# M_B_adapter_414.net
KiCad netlist of a schematic drawn in EAGLE
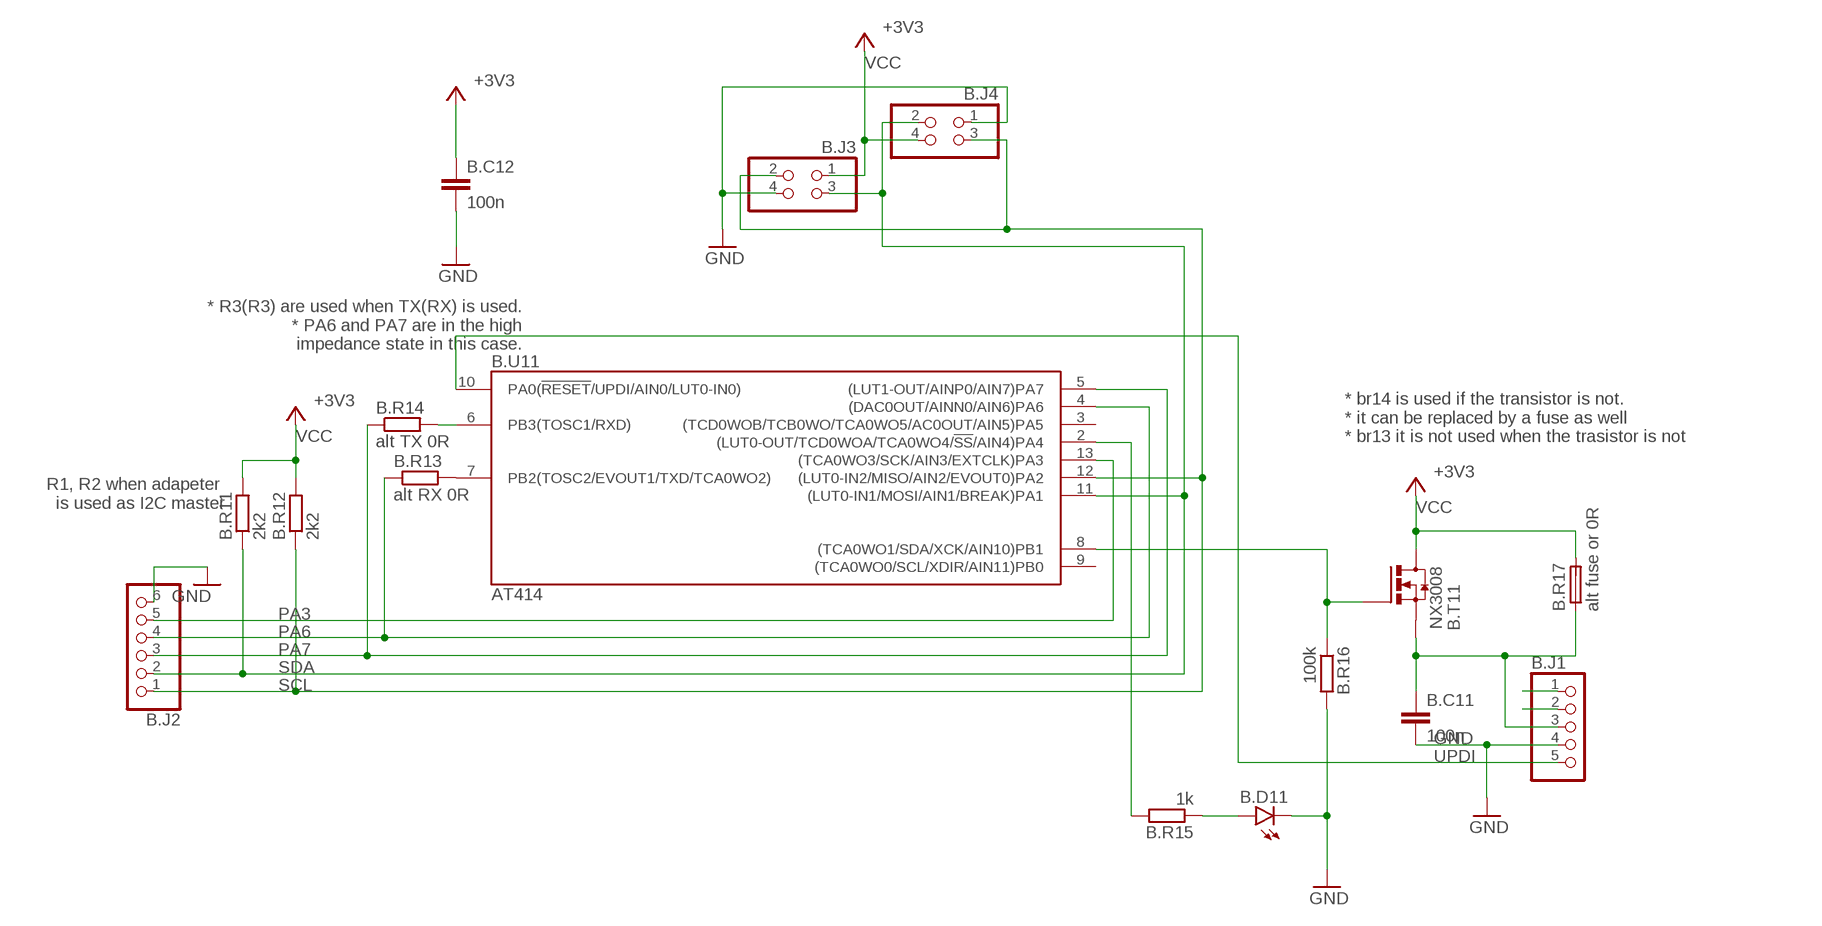
[diagram p0: schematic, sheet 1]

(export (version "E")
  (design (tool "Eeschema 10.0.6"))
  (components
    (comp (ref "B.C11")
      (value "100n")
      (footprint "eagle-import:C0603")
      (libsource (lib "eagle-import") (part "C-EUC0603"))
    )
    (comp (ref "B.C12")
      (value "100n")
      (footprint "eagle-import:C0603")
      (libsource (lib "eagle-import") (part "C-EUC0603"))
    )
    (comp (ref "B.D11")
      (value "LEDCHIP-LED0603")
      (footprint "eagle-import:CHIP-LED0603")
      (libsource (lib "eagle-import") (part "LEDCHIP-LED0603"))
    )
    (comp (ref "B.J1")
      (value "PINHD-1X5")
      (footprint "eagle-import:1X05")
      (libsource (lib "eagle-import") (part "PINHD-1X5"))
    )
    (comp (ref "B.J2")
      (value "PINHD-1X6")
      (footprint "eagle-import:1X06")
      (libsource (lib "eagle-import") (part "PINHD-1X6"))
    )
    (comp (ref "B.J3")
      (value "PINHD-2X2")
      (footprint "eagle-import:2X02")
      (libsource (lib "eagle-import") (part "PINHD-2X2"))
    )
    (comp (ref "B.J4")
      (value "PINHD-2X2")
      (footprint "eagle-import:2X02")
      (libsource (lib "eagle-import") (part "PINHD-2X2"))
    )
    (comp (ref "B.R11")
      (value "2k2")
      (footprint "eagle-import:R0603")
      (libsource (lib "eagle-import") (part "R-EU_R0603"))
    )
    (comp (ref "B.R12")
      (value "2k2")
      (footprint "eagle-import:R0603")
      (libsource (lib "eagle-import") (part "R-EU_R0603"))
    )
    (comp (ref "B.R13")
      (value "alt RX 0R")
      (footprint "eagle-import:R0603")
      (libsource (lib "eagle-import") (part "R-EU_R0603"))
    )
    (comp (ref "B.R14")
      (value "alt TX 0R")
      (footprint "eagle-import:R0603")
      (libsource (lib "eagle-import") (part "R-EU_R0603"))
    )
    (comp (ref "B.R15")
      (value "1k")
      (footprint "eagle-import:R0603")
      (libsource (lib "eagle-import") (part "R-EU_R0603"))
    )
    (comp (ref "B.R16")
      (value "100k")
      (footprint "eagle-import:R0603")
      (libsource (lib "eagle-import") (part "R-EU_R0603"))
    )
    (comp (ref "B.R17")
      (value "alt fuse or 0R")
      (footprint "eagle-import:FUSE")
      (libsource (lib "eagle-import") (part "FUSE"))
    )
    (comp (ref "B.T11")
      (value "NX3008")
      (footprint "eagle-import:SO23")
      (libsource (lib "eagle-import") (part "N-MOSFET"))
    )
    (comp (ref "B.U11")
      (value "AT414")
      (footprint "eagle-import:SO14")
      (libsource (lib "eagle-import") (part "ATTINY14-SSN4"))
    )
  )
  (nets
    (net (code "1") (name "+3V3") (class "Default")
      (node (ref "B.C12") (pin "1") (pinfunction "1_1") (pintype "passive"))
      (node (ref "B.J3") (pin "1") (pinfunction "1_1") (pintype "passive"))
      (node (ref "B.J4") (pin "4") (pinfunction "4_4") (pintype "passive"))
      (node (ref "B.R11") (pin "2") (pinfunction "2_2") (pintype "passive"))
      (node (ref "B.R12") (pin "2") (pinfunction "2_2") (pintype "passive"))
      (node (ref "B.R17") (pin "2") (pinfunction "2_2") (pintype "passive"))
      (node (ref "B.T11") (pin "D") (pinfunction "D_D") (pintype "passive"))
    )
    (net (code "2") (name "/PA3") (class "Default")
      (node (ref "B.J2") (pin "5") (pinfunction "5_5") (pintype "passive"))
      (node (ref "B.U11") (pin "13") (pinfunction "(TCA0WO3/SCK/AIN3/EXTCLK)PA3_13") (pintype "bidirectional"))
    )
    (net (code "3") (name "/PA6") (class "Default")
      (node (ref "B.J2") (pin "4") (pinfunction "4_4") (pintype "passive"))
      (node (ref "B.R13") (pin "1") (pinfunction "1_1") (pintype "passive"))
      (node (ref "B.U11") (pin "4") (pinfunction "(DAC0OUT/AINN0/AIN6)PA6_4") (pintype "bidirectional"))
    )
    (net (code "4") (name "/PA7") (class "Default")
      (node (ref "B.J2") (pin "3") (pinfunction "3_3") (pintype "passive"))
      (node (ref "B.R14") (pin "1") (pinfunction "1_1") (pintype "passive"))
      (node (ref "B.U11") (pin "5") (pinfunction "(LUT1-OUT/AINP0/AIN7)PA7_5") (pintype "bidirectional"))
    )
    (net (code "5") (name "/SCL") (class "Default")
      (node (ref "B.J2") (pin "1") (pinfunction "1_1") (pintype "passive"))
      (node (ref "B.J3") (pin "2") (pinfunction "2_2") (pintype "passive"))
      (node (ref "B.J4") (pin "3") (pinfunction "3_3") (pintype "passive"))
      (node (ref "B.R12") (pin "1") (pinfunction "1_1") (pintype "passive"))
      (node (ref "B.U11") (pin "12") (pinfunction "(LUT0-IN2/MISO/AIN2/EVOUT0)PA2_12") (pintype "bidirectional"))
    )
    (net (code "6") (name "/SDA") (class "Default")
      (node (ref "B.J2") (pin "2") (pinfunction "2_2") (pintype "passive"))
      (node (ref "B.J3") (pin "3") (pinfunction "3_3") (pintype "passive"))
      (node (ref "B.J4") (pin "2") (pinfunction "2_2") (pintype "passive"))
      (node (ref "B.R11") (pin "1") (pinfunction "1_1") (pintype "passive"))
      (node (ref "B.U11") (pin "11") (pinfunction "(LUT0-IN1/MOSI/AIN1/BREAK)PA1_11") (pintype "bidirectional"))
    )
    (net (code "7") (name "/UPDI") (class "Default")
      (node (ref "B.J1") (pin "5") (pinfunction "5_5") (pintype "passive"))
      (node (ref "B.U11") (pin "10") (pinfunction "PA0(~{RESET}/UPDI/AIN0/LUT0-IN0)_10") (pintype "bidirectional"))
    )
    (net (code "8") (name "GND") (class "Default")
      (node (ref "B.C11") (pin "2") (pinfunction "2_2") (pintype "passive"))
      (node (ref "B.C12") (pin "2") (pinfunction "2_2") (pintype "passive"))
      (node (ref "B.D11") (pin "C1") (pinfunction "C_C1") (pintype "passive"))
      (node (ref "B.J1") (pin "4") (pinfunction "4_4") (pintype "passive"))
      (node (ref "B.J2") (pin "6") (pinfunction "6_6") (pintype "passive"))
      (node (ref "B.J3") (pin "4") (pinfunction "4_4") (pintype "passive"))
      (node (ref "B.J4") (pin "1") (pinfunction "1_1") (pintype "passive"))
      (node (ref "B.R16") (pin "2") (pinfunction "2_2") (pintype "passive"))
    )
    (net (code "9") (name "Net-(B.C11-Pad1)") (class "Default")
      (node (ref "B.C11") (pin "1") (pinfunction "1_1") (pintype "passive"))
      (node (ref "B.J1") (pin "3") (pinfunction "3_3") (pintype "passive"))
      (node (ref "B.R17") (pin "1") (pinfunction "1_1") (pintype "passive"))
      (node (ref "B.T11") (pin "S") (pinfunction "S_S") (pintype "passive"))
    )
    (net (code "10") (name "Net-(B.D11-A)") (class "Default")
      (node (ref "B.D11") (pin "A1") (pinfunction "A_A1") (pintype "passive"))
      (node (ref "B.R15") (pin "1") (pinfunction "1_1") (pintype "passive"))
    )
    (net (code "11") (name "Net-(B.U11A-(LUT0-OUT{slash}TCD0WOA{slash}TCA0WO4{slash}~{SS}{slash}AIN4)PA4)") (class "Default")
      (node (ref "B.R15") (pin "2") (pinfunction "2_2") (pintype "passive"))
      (node (ref "B.U11") (pin "2") (pinfunction "(LUT0-OUT/TCD0WOA/TCA0WO4/~{SS}/AIN4)PA4_2") (pintype "bidirectional"))
    )
    (net (code "12") (name "Net-(B.U11A-(TCA0WO1{slash}SDA{slash}XCK{slash}AIN10)PB1)") (class "Default")
      (node (ref "B.R16") (pin "1") (pinfunction "1_1") (pintype "passive"))
      (node (ref "B.T11") (pin "G") (pinfunction "G_G") (pintype "passive"))
      (node (ref "B.U11") (pin "8") (pinfunction "(TCA0WO1/SDA/XCK/AIN10)PB1_8") (pintype "bidirectional"))
    )
    (net (code "13") (name "Net-(B.U11A-PB2(TOSC2{slash}EVOUT1{slash}TXD{slash}TCA0WO2))") (class "Default")
      (node (ref "B.R13") (pin "2") (pinfunction "2_2") (pintype "passive"))
      (node (ref "B.U11") (pin "7") (pinfunction "PB2(TOSC2/EVOUT1/TXD/TCA0WO2)_7") (pintype "bidirectional"))
    )
    (net (code "14") (name "Net-(B.U11A-PB3(TOSC1{slash}RXD))") (class "Default")
      (node (ref "B.R14") (pin "2") (pinfunction "2_2") (pintype "passive"))
      (node (ref "B.U11") (pin "6") (pinfunction "PB3(TOSC1/RXD)_6") (pintype "bidirectional"))
    )
    (net (code "15") (name "unconnected-(B.J1-Pad1)") (class "Default")
      (node (ref "B.J1") (pin "1") (pinfunction "1_1") (pintype "passive"))
    )
    (net (code "16") (name "unconnected-(B.J1-Pad2)") (class "Default")
      (node (ref "B.J1") (pin "2") (pinfunction "2_2") (pintype "passive"))
    )
    (net (code "17") (name "unconnected-(B.U11A-(TCA0WO0{slash}SCL{slash}XDIR{slash}AIN11)PB0-Pad9)") (class "Default")
      (node (ref "B.U11") (pin "9") (pinfunction "(TCA0WO0/SCL/XDIR/AIN11)PB0_9") (pintype "bidirectional"))
    )
    (net (code "18") (name "unconnected-(B.U11A-(TCD0WOB{slash}TCB0WO{slash}TCA0WO5{slash}AC0OUT{slash}AIN5)PA5-Pad3)") (class "Default")
      (node (ref "B.U11") (pin "3") (pinfunction "(TCD0WOB/TCB0WO/TCA0WO5/AC0OUT/AIN5)PA5_3") (pintype "bidirectional"))
    )
  )
)
